# Digital_IN.net
KiCad netlist of a schematic drawn in Altium Designer
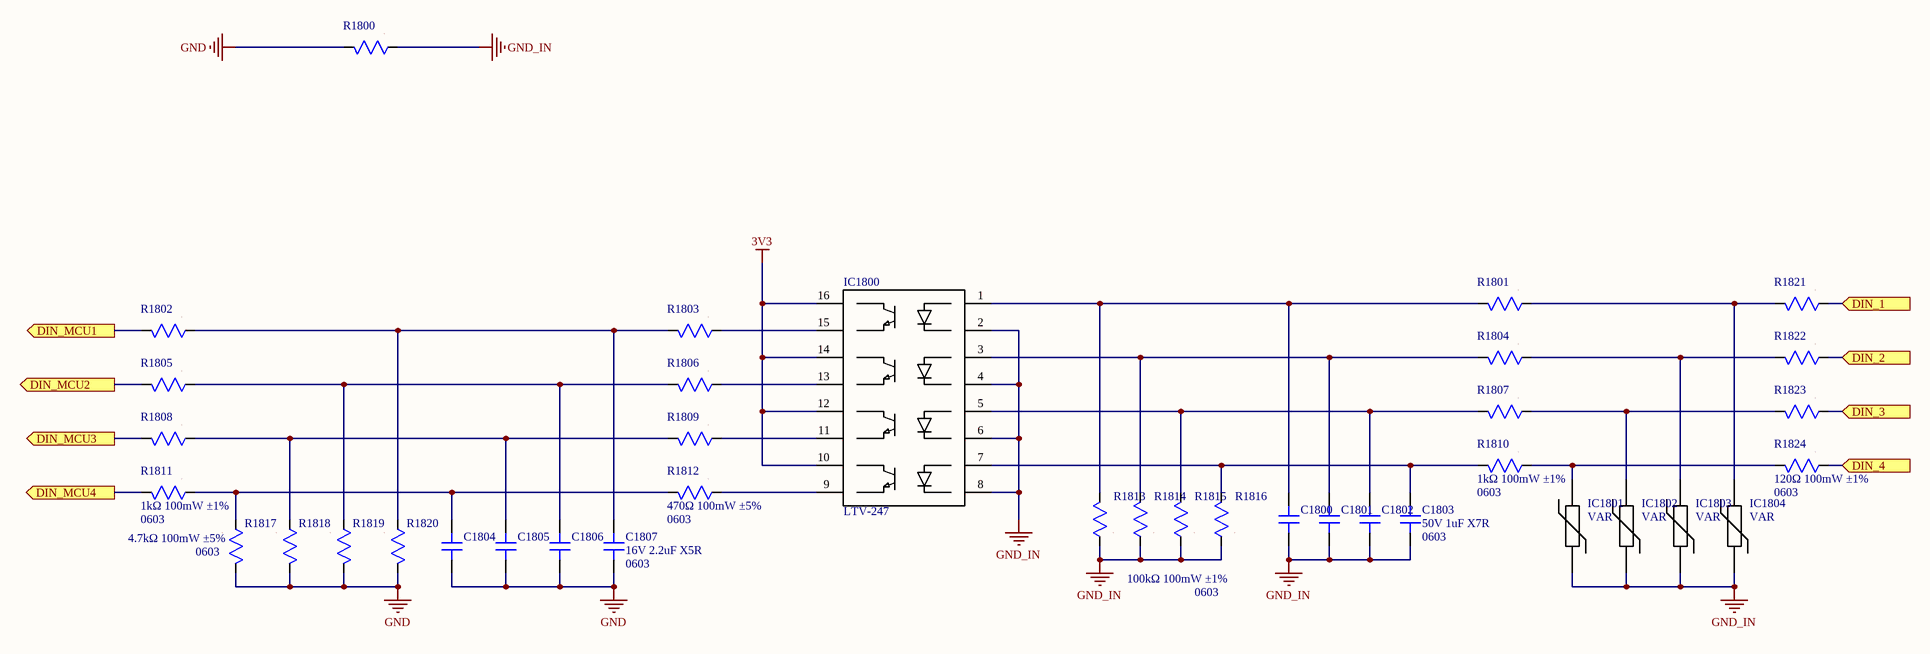
[diagram p0: Digital_IN.SchDoc]

(export (version "E")
  (design (tool "Eeschema 10.0.6"))
  (components
    (comp (ref "C1800")
      (value "CAP non polarized")
      (footprint "CAP SMD 0603")
      (description "Condensadores de cerámica multicapa (MLCC- SMD/SMT) WCAP-CSGP 1uF 50 Vol 10%")
      (fields (field (name "MPN") "885012206126") (field (name "MANUFACTURER") "Wurth Elektronik"))
      (libsource (lib "eUSR_Database") (part "CAP non polarized"))
    )
    (comp (ref "C1801")
      (value "CAP non polarized")
      (footprint "CAP SMD 0603")
      (description "Condensadores de cerámica multicapa (MLCC- SMD/SMT) WCAP-CSGP 1uF 50 Vol 10%")
      (fields (field (name "MPN") "885012206126") (field (name "MANUFACTURER") "Wurth Elektronik"))
      (libsource (lib "eUSR_Database") (part "CAP non polarized"))
    )
    (comp (ref "C1802")
      (value "CAP non polarized")
      (footprint "CAP SMD 0603")
      (description "Condensadores de cerámica multicapa (MLCC- SMD/SMT) WCAP-CSGP 1uF 50 Vol 10%")
      (fields (field (name "MPN") "885012206126") (field (name "MANUFACTURER") "Wurth Elektronik"))
      (libsource (lib "eUSR_Database") (part "CAP non polarized"))
    )
    (comp (ref "C1803")
      (value "50V 1uF X7R")
      (footprint "CAP SMD 0603")
      (description "Condensadores de cerámica multicapa (MLCC- SMD/SMT) WCAP-CSGP 1uF 50 Vol 10%")
      (fields
        (field (name "PACKAGE") "0603")
        (field (name "MPN") "885012206126")
        (field (name "MANUFACTURER") "Wurth Elektronik")
      )
      (libsource (lib "eUSR_Database") (part "CAP non polarized"))
    )
    (comp (ref "C1804")
      (value "CAP non polarized")
      (footprint "CAP SMD 0603")
      (description "Condensadores de cerámica multicapa (MLCC- SMD/SMT) WCAP-CSGP 2.2uF 16V 10%")
      (fields (field (name "MPN") "885012106029") (field (name "MANUFACTURER") "Wurth Elektronik"))
      (libsource (lib "eUSR_Database") (part "CAP non polarized"))
    )
    (comp (ref "C1805")
      (value "CAP non polarized")
      (footprint "CAP SMD 0603")
      (description "Condensadores de cerámica multicapa (MLCC- SMD/SMT) WCAP-CSGP 2.2uF 16V 10%")
      (fields (field (name "MPN") "885012106029") (field (name "MANUFACTURER") "Wurth Elektronik"))
      (libsource (lib "eUSR_Database") (part "CAP non polarized"))
    )
    (comp (ref "C1806")
      (value "CAP non polarized")
      (footprint "CAP SMD 0603")
      (description "Condensadores de cerámica multicapa (MLCC- SMD/SMT) WCAP-CSGP 2.2uF 16V 10%")
      (fields (field (name "MPN") "885012106029") (field (name "MANUFACTURER") "Wurth Elektronik"))
      (libsource (lib "eUSR_Database") (part "CAP non polarized"))
    )
    (comp (ref "C1807")
      (value "16V 2.2uF X5R")
      (footprint "CAP SMD 0603")
      (description "Condensadores de cerámica multicapa (MLCC- SMD/SMT) WCAP-CSGP 2.2uF 16V 10%")
      (fields
        (field (name "PACKAGE") "0603")
        (field (name "MPN") "885012106029")
        (field (name "MANUFACTURER") "Wurth Elektronik")
      )
      (libsource (lib "eUSR_Database") (part "CAP non polarized"))
    )
    (comp (ref "IC1800")
      (value "LTV-247")
      (footprint "SOP-16")
      (description "Optoacopladores para salidas de transistores PTR 50% 5KV 16 PIN 4CH Optocoupler")
      (fields (field (name "MANUFACTURER") "LITEON"))
      (libsource (lib "eUSR_Database") (part "LTV-247"))
    )
    (comp (ref "IC1801")
      (value "VAR")
      (footprint "VAR SMD 0805")
      (description "Varistores 18 VDC .3J 44V-CL 120A PK")
      (fields (field (name "MPN") "V18MLA0805NH") (field (name "MANUFACTURER") "Littlefuse"))
      (libsource (lib "eUSR_Database") (part "VAR"))
    )
    (comp (ref "IC1802")
      (value "VAR")
      (footprint "VAR SMD 0805")
      (description "Varistores 18 VDC .3J 44V-CL 120A PK")
      (fields (field (name "MPN") "V18MLA0805NH") (field (name "MANUFACTURER") "Littlefuse"))
      (libsource (lib "eUSR_Database") (part "VAR"))
    )
    (comp (ref "IC1803")
      (value "VAR")
      (footprint "VAR SMD 0805")
      (description "Varistores 18 VDC .3J 44V-CL 120A PK")
      (fields (field (name "MPN") "V18MLA0805NH") (field (name "MANUFACTURER") "Littlefuse"))
      (libsource (lib "eUSR_Database") (part "VAR"))
    )
    (comp (ref "IC1804")
      (value "VAR")
      (footprint "VAR SMD 0805")
      (description "Varistores 18 VDC .3J 44V-CL 120A PK")
      (fields (field (name "MPN") "V18MLA0805NH") (field (name "MANUFACTURER") "Littlefuse"))
      (libsource (lib "eUSR_Database") (part "VAR"))
    )
    (comp (ref "R1800")
      (value "RES")
      (footprint "RES SMD 0603")
      (description "Resistores de película gruesa - SMD WRIS-RSKS <0.05 Ohms 0.1 W Jumper 0603 AEC-Q200")
      (fields (field (name "MPN") "560112116001") (field (name "MANUFACTURER") "Wurth Elektronik"))
      (libsource (lib "eUSR_Database") (part "RES"))
    )
    (comp (ref "R1801")
      (value "RES")
      (footprint "RES SMD 0603")
      (description "Thick Film Resistors WRIS-RSKS 1 kOhms 1 % 0.1 W 0603 AEC-Q200")
      (fields (field (name "MPN") "560112116014") (field (name "MANUFACTURER") "Wurth Elektronik"))
      (libsource (lib "eUSR_Database") (part "RES"))
    )
    (comp (ref "R1802")
      (value "RES")
      (footprint "RES SMD 0603")
      (description "Thick Film Resistors WRIS-RSKS 1 kOhms 1 % 0.1 W 0603 AEC-Q200")
      (fields (field (name "MPN") "560112116014") (field (name "MANUFACTURER") "Wurth Elektronik"))
      (libsource (lib "eUSR_Database") (part "RES"))
    )
    (comp (ref "R1803")
      (value "RES")
      (footprint "RES SMD 0603")
      (description "Thick Film Resistors WRIS-RSKS 470 Ohms 5 % 0.1 W 0603 AEC-Q200")
      (fields (field (name "MPN") "560112116031") (field (name "MANUFACTURER") "Wurth Elektronik"))
      (libsource (lib "eUSR_Database") (part "RES"))
    )
    (comp (ref "R1804")
      (value "RES")
      (footprint "RES SMD 0603")
      (description "Thick Film Resistors WRIS-RSKS 1 kOhms 1 % 0.1 W 0603 AEC-Q200")
      (fields (field (name "MPN") "560112116014") (field (name "MANUFACTURER") "Wurth Elektronik"))
      (libsource (lib "eUSR_Database") (part "RES"))
    )
    (comp (ref "R1805")
      (value "RES")
      (footprint "RES SMD 0603")
      (description "Thick Film Resistors WRIS-RSKS 1 kOhms 1 % 0.1 W 0603 AEC-Q200")
      (fields (field (name "MPN") "560112116014") (field (name "MANUFACTURER") "Wurth Elektronik"))
      (libsource (lib "eUSR_Database") (part "RES"))
    )
    (comp (ref "R1806")
      (value "RES")
      (footprint "RES SMD 0603")
      (description "Thick Film Resistors WRIS-RSKS 470 Ohms 5 % 0.1 W 0603 AEC-Q200")
      (fields (field (name "MPN") "560112116031") (field (name "MANUFACTURER") "Wurth Elektronik"))
      (libsource (lib "eUSR_Database") (part "RES"))
    )
    (comp (ref "R1807")
      (value "RES")
      (footprint "RES SMD 0603")
      (description "Thick Film Resistors WRIS-RSKS 1 kOhms 1 % 0.1 W 0603 AEC-Q200")
      (fields (field (name "MPN") "560112116014") (field (name "MANUFACTURER") "Wurth Elektronik"))
      (libsource (lib "eUSR_Database") (part "RES"))
    )
    (comp (ref "R1808")
      (value "RES")
      (footprint "RES SMD 0603")
      (description "Thick Film Resistors WRIS-RSKS 1 kOhms 1 % 0.1 W 0603 AEC-Q200")
      (fields (field (name "MPN") "560112116014") (field (name "MANUFACTURER") "Wurth Elektronik"))
      (libsource (lib "eUSR_Database") (part "RES"))
    )
    (comp (ref "R1809")
      (value "RES")
      (footprint "RES SMD 0603")
      (description "Thick Film Resistors WRIS-RSKS 470 Ohms 5 % 0.1 W 0603 AEC-Q200")
      (fields (field (name "MPN") "560112116031") (field (name "MANUFACTURER") "Wurth Elektronik"))
      (libsource (lib "eUSR_Database") (part "RES"))
    )
    (comp (ref "R1810")
      (value "1kΩ 100mW ±1%")
      (footprint "RES SMD 0603")
      (description "Thick Film Resistors WRIS-RSKS 1 kOhms 1 % 0.1 W 0603 AEC-Q200")
      (fields
        (field (name "PACKAGE") "0603")
        (field (name "MPN") "560112116014")
        (field (name "MANUFACTURER") "Wurth Elektronik")
      )
      (libsource (lib "eUSR_Database") (part "RES"))
    )
    (comp (ref "R1811")
      (value "1kΩ 100mW ±1%")
      (footprint "RES SMD 0603")
      (description "Thick Film Resistors WRIS-RSKS 1 kOhms 1 % 0.1 W 0603 AEC-Q200")
      (fields
        (field (name "PACKAGE") "0603")
        (field (name "MPN") "560112116014")
        (field (name "MANUFACTURER") "Wurth Elektronik")
      )
      (libsource (lib "eUSR_Database") (part "RES"))
    )
    (comp (ref "R1812")
      (value "470Ω 100mW ±5%")
      (footprint "RES SMD 0603")
      (description "Thick Film Resistors WRIS-RSKS 470 Ohms 5 % 0.1 W 0603 AEC-Q200")
      (fields
        (field (name "PACKAGE") "0603")
        (field (name "MPN") "560112116031")
        (field (name "MANUFACTURER") "Wurth Elektronik")
      )
      (libsource (lib "eUSR_Database") (part "RES"))
    )
    (comp (ref "R1813")
      (value "100kΩ 100mW ±1%")
      (footprint "RES SMD 0603")
      (description "Thick Film Resistors WRIS-RSKS 100 kOhms 1 % 0.1 W 0603 AEC-Q200")
      (fields
        (field (name "PACKAGE") "0603")
        (field (name "MPN") "560112116004")
        (field (name "MANUFACTURER") "Wurth Elektronik")
      )
      (libsource (lib "eUSR_Database") (part "RES"))
    )
    (comp (ref "R1814")
      (value "RES")
      (footprint "RES SMD 0603")
      (description "Thick Film Resistors WRIS-RSKS 100 kOhms 1 % 0.1 W 0603 AEC-Q200")
      (fields (field (name "MPN") "560112116004") (field (name "MANUFACTURER") "Wurth Elektronik"))
      (libsource (lib "eUSR_Database") (part "RES"))
    )
    (comp (ref "R1815")
      (value "RES")
      (footprint "RES SMD 0603")
      (description "Thick Film Resistors WRIS-RSKS 100 kOhms 1 % 0.1 W 0603 AEC-Q200")
      (fields (field (name "MPN") "560112116004") (field (name "MANUFACTURER") "Wurth Elektronik"))
      (libsource (lib "eUSR_Database") (part "RES"))
    )
    (comp (ref "R1816")
      (value "RES")
      (footprint "RES SMD 0603")
      (description "Thick Film Resistors WRIS-RSKS 100 kOhms 1 % 0.1 W 0603 AEC-Q200")
      (fields (field (name "MPN") "560112116004") (field (name "MANUFACTURER") "Wurth Elektronik"))
      (libsource (lib "eUSR_Database") (part "RES"))
    )
    (comp (ref "R1817")
      (value "4.7kΩ 100mW ±5%")
      (footprint "RES SMD 0603")
      (description "Thick Film Resistors WRIS-RSKS 4.7 kOhms 5 % 0.1 W 0402 AEC-Q200")
      (fields
        (field (name "PACKAGE") "0603")
        (field (name "MPN") "560112110018")
        (field (name "MANUFACTURER") "Wurth Elektronik")
      )
      (libsource (lib "eUSR_Database") (part "RES"))
    )
    (comp (ref "R1818")
      (value "RES")
      (footprint "RES SMD 0603")
      (description "Thick Film Resistors WRIS-RSKS 4.7 kOhms 5 % 0.1 W 0402 AEC-Q200")
      (fields (field (name "MPN") "560112110018") (field (name "MANUFACTURER") "Wurth Elektronik"))
      (libsource (lib "eUSR_Database") (part "RES"))
    )
    (comp (ref "R1819")
      (value "RES")
      (footprint "RES SMD 0603")
      (description "Thick Film Resistors WRIS-RSKS 4.7 kOhms 5 % 0.1 W 0402 AEC-Q200")
      (fields (field (name "MPN") "560112110018") (field (name "MANUFACTURER") "Wurth Elektronik"))
      (libsource (lib "eUSR_Database") (part "RES"))
    )
    (comp (ref "R1820")
      (value "RES")
      (footprint "RES SMD 0603")
      (description "Thick Film Resistors WRIS-RSKS 4.7 kOhms 5 % 0.1 W 0402 AEC-Q200")
      (fields (field (name "MPN") "560112110018") (field (name "MANUFACTURER") "Wurth Elektronik"))
      (libsource (lib "eUSR_Database") (part "RES"))
    )
    (comp (ref "R1821")
      (value "RES")
      (footprint "RES SMD 0603")
      (description "Resistores de película gruesa - SMD WRIS-RSKS 120 Ohms 1 % 0.1 W 0603 AEC-Q200")
      (fields (field (name "MPN") "560112116119") (field (name "MANUFACTURER") "Wurth Elektronik"))
      (libsource (lib "eUSR_Database") (part "RES"))
    )
    (comp (ref "R1822")
      (value "RES")
      (footprint "RES SMD 0603")
      (description "Resistores de película gruesa - SMD WRIS-RSKS 120 Ohms 1 % 0.1 W 0603 AEC-Q200")
      (fields (field (name "MPN") "560112116119") (field (name "MANUFACTURER") "Wurth Elektronik"))
      (libsource (lib "eUSR_Database") (part "RES"))
    )
    (comp (ref "R1823")
      (value "RES")
      (footprint "RES SMD 0603")
      (description "Resistores de película gruesa - SMD WRIS-RSKS 120 Ohms 1 % 0.1 W 0603 AEC-Q200")
      (fields (field (name "MPN") "560112116119") (field (name "MANUFACTURER") "Wurth Elektronik"))
      (libsource (lib "eUSR_Database") (part "RES"))
    )
    (comp (ref "R1824")
      (value "120Ω 100mW ±1%")
      (footprint "RES SMD 0603")
      (description "Resistores de película gruesa - SMD WRIS-RSKS 120 Ohms 1 % 0.1 W 0603 AEC-Q200")
      (fields
        (field (name "PACKAGE") "0603")
        (field (name "MPN") "560112116119")
        (field (name "MANUFACTURER") "Wurth Elektronik")
      )
      (libsource (lib "eUSR_Database") (part "RES"))
    )
  )
  (nets
    (net (code "1") (name "/DIN_1") (class "Default")
      (node (ref "R1821") (pin "1") (pinfunction "1_1") (pintype "passive"))
    )
    (net (code "2") (name "/DIN_2") (class "Default")
      (node (ref "R1822") (pin "1") (pinfunction "1_1") (pintype "passive"))
    )
    (net (code "3") (name "/DIN_3") (class "Default")
      (node (ref "R1823") (pin "1") (pinfunction "1_1") (pintype "passive"))
    )
    (net (code "4") (name "/DIN_4") (class "Default")
      (node (ref "R1824") (pin "1") (pinfunction "1_1") (pintype "passive"))
    )
    (net (code "5") (name "/DIN_MCU1") (class "Default")
      (node (ref "R1802") (pin "2") (pinfunction "2_2") (pintype "passive"))
    )
    (net (code "6") (name "/DIN_MCU2") (class "Default")
      (node (ref "R1805") (pin "2") (pinfunction "2_2") (pintype "passive"))
    )
    (net (code "7") (name "/DIN_MCU3") (class "Default")
      (node (ref "R1808") (pin "2") (pinfunction "2_2") (pintype "passive"))
    )
    (net (code "8") (name "/DIN_MCU4") (class "Default")
      (node (ref "R1811") (pin "2") (pinfunction "2_2") (pintype "passive"))
    )
    (net (code "9") (name "3V3") (class "Default")
      (node (ref "IC1800") (pin "10") (pinfunction "C_4_10") (pintype "passive"))
      (node (ref "IC1800") (pin "12") (pinfunction "C_3_12") (pintype "passive"))
      (node (ref "IC1800") (pin "14") (pinfunction "C_2_14") (pintype "passive"))
      (node (ref "IC1800") (pin "16") (pinfunction "C_1_16") (pintype "passive"))
    )
    (net (code "10") (name "GND") (class "Default")
      (node (ref "C1804") (pin "2") (pinfunction "2_2") (pintype "passive"))
      (node (ref "C1805") (pin "2") (pinfunction "2_2") (pintype "passive"))
      (node (ref "C1806") (pin "2") (pinfunction "2_2") (pintype "passive"))
      (node (ref "C1807") (pin "2") (pinfunction "2_2") (pintype "passive"))
      (node (ref "R1800") (pin "2") (pinfunction "2_2") (pintype "passive"))
      (node (ref "R1817") (pin "2") (pinfunction "2_2") (pintype "passive"))
      (node (ref "R1818") (pin "2") (pinfunction "2_2") (pintype "passive"))
      (node (ref "R1819") (pin "2") (pinfunction "2_2") (pintype "passive"))
      (node (ref "R1820") (pin "2") (pinfunction "2_2") (pintype "passive"))
    )
    (net (code "11") (name "GND_IN") (class "Default")
      (node (ref "C1800") (pin "2") (pinfunction "2_2") (pintype "passive"))
      (node (ref "C1801") (pin "2") (pinfunction "2_2") (pintype "passive"))
      (node (ref "C1802") (pin "2") (pinfunction "2_2") (pintype "passive"))
      (node (ref "C1803") (pin "2") (pinfunction "2_2") (pintype "passive"))
      (node (ref "IC1800") (pin "2") (pinfunction "K_1_2") (pintype "passive"))
      (node (ref "IC1800") (pin "4") (pinfunction "K_2_4") (pintype "passive"))
      (node (ref "IC1800") (pin "6") (pinfunction "K_3_6") (pintype "passive"))
      (node (ref "IC1800") (pin "8") (pinfunction "K_4_8") (pintype "passive"))
      (node (ref "IC1801") (pin "1") (pinfunction "1_1") (pintype "passive"))
      (node (ref "IC1802") (pin "1") (pinfunction "1_1") (pintype "passive"))
      (node (ref "IC1803") (pin "1") (pinfunction "1_1") (pintype "passive"))
      (node (ref "IC1804") (pin "1") (pinfunction "1_1") (pintype "passive"))
      (node (ref "R1800") (pin "1") (pinfunction "1_1") (pintype "passive"))
      (node (ref "R1813") (pin "1") (pinfunction "1_1") (pintype "passive"))
      (node (ref "R1814") (pin "1") (pinfunction "1_1") (pintype "passive"))
      (node (ref "R1815") (pin "1") (pinfunction "1_1") (pintype "passive"))
      (node (ref "R1816") (pin "1") (pinfunction "1_1") (pintype "passive"))
    )
    (net (code "12") (name "Net-(C1804-Pad1)") (class "Default")
      (node (ref "C1804") (pin "1") (pinfunction "1_1") (pintype "passive"))
      (node (ref "R1811") (pin "1") (pinfunction "1_1") (pintype "passive"))
      (node (ref "R1812") (pin "2") (pinfunction "2_2") (pintype "passive"))
      (node (ref "R1817") (pin "1") (pinfunction "1_1") (pintype "passive"))
    )
    (net (code "13") (name "Net-(C1805-Pad1)") (class "Default")
      (node (ref "C1805") (pin "1") (pinfunction "1_1") (pintype "passive"))
      (node (ref "R1808") (pin "1") (pinfunction "1_1") (pintype "passive"))
      (node (ref "R1809") (pin "2") (pinfunction "2_2") (pintype "passive"))
      (node (ref "R1818") (pin "1") (pinfunction "1_1") (pintype "passive"))
    )
    (net (code "14") (name "Net-(C1806-Pad1)") (class "Default")
      (node (ref "C1806") (pin "1") (pinfunction "1_1") (pintype "passive"))
      (node (ref "R1805") (pin "1") (pinfunction "1_1") (pintype "passive"))
      (node (ref "R1806") (pin "2") (pinfunction "2_2") (pintype "passive"))
      (node (ref "R1819") (pin "1") (pinfunction "1_1") (pintype "passive"))
    )
    (net (code "15") (name "Net-(C1807-Pad1)") (class "Default")
      (node (ref "C1807") (pin "1") (pinfunction "1_1") (pintype "passive"))
      (node (ref "R1802") (pin "1") (pinfunction "1_1") (pintype "passive"))
      (node (ref "R1803") (pin "2") (pinfunction "2_2") (pintype "passive"))
      (node (ref "R1820") (pin "1") (pinfunction "1_1") (pintype "passive"))
    )
    (net (code "16") (name "Net-(IC1800-A_1)") (class "Default")
      (node (ref "C1800") (pin "1") (pinfunction "1_1") (pintype "passive"))
      (node (ref "IC1800") (pin "1") (pinfunction "A_1_1") (pintype "passive"))
      (node (ref "R1801") (pin "2") (pinfunction "2_2") (pintype "passive"))
      (node (ref "R1813") (pin "2") (pinfunction "2_2") (pintype "passive"))
    )
    (net (code "17") (name "Net-(IC1800-A_2)") (class "Default")
      (node (ref "C1801") (pin "1") (pinfunction "1_1") (pintype "passive"))
      (node (ref "IC1800") (pin "3") (pinfunction "A_2_3") (pintype "passive"))
      (node (ref "R1804") (pin "2") (pinfunction "2_2") (pintype "passive"))
      (node (ref "R1814") (pin "2") (pinfunction "2_2") (pintype "passive"))
    )
    (net (code "18") (name "Net-(IC1800-A_3)") (class "Default")
      (node (ref "C1802") (pin "1") (pinfunction "1_1") (pintype "passive"))
      (node (ref "IC1800") (pin "5") (pinfunction "A_3_5") (pintype "passive"))
      (node (ref "R1807") (pin "2") (pinfunction "2_2") (pintype "passive"))
      (node (ref "R1815") (pin "2") (pinfunction "2_2") (pintype "passive"))
    )
    (net (code "19") (name "Net-(IC1800-A_4)") (class "Default")
      (node (ref "C1803") (pin "1") (pinfunction "1_1") (pintype "passive"))
      (node (ref "IC1800") (pin "7") (pinfunction "A_4_7") (pintype "passive"))
      (node (ref "R1810") (pin "2") (pinfunction "2_2") (pintype "passive"))
      (node (ref "R1816") (pin "2") (pinfunction "2_2") (pintype "passive"))
    )
    (net (code "20") (name "Net-(IC1800-E_1)") (class "Default")
      (node (ref "IC1800") (pin "15") (pinfunction "E_1_15") (pintype "passive"))
      (node (ref "R1803") (pin "1") (pinfunction "1_1") (pintype "passive"))
    )
    (net (code "21") (name "Net-(IC1800-E_2)") (class "Default")
      (node (ref "IC1800") (pin "13") (pinfunction "E_2_13") (pintype "passive"))
      (node (ref "R1806") (pin "1") (pinfunction "1_1") (pintype "passive"))
    )
    (net (code "22") (name "Net-(IC1800-E_3)") (class "Default")
      (node (ref "IC1800") (pin "11") (pinfunction "E_3_11") (pintype "passive"))
      (node (ref "R1809") (pin "1") (pinfunction "1_1") (pintype "passive"))
    )
    (net (code "23") (name "Net-(IC1800-E_4)") (class "Default")
      (node (ref "IC1800") (pin "9") (pinfunction "E_4_9") (pintype "passive"))
      (node (ref "R1812") (pin "1") (pinfunction "1_1") (pintype "passive"))
    )
    (net (code "24") (name "Net-(IC1801-Pad2)") (class "Default")
      (node (ref "IC1801") (pin "2") (pinfunction "2_2") (pintype "passive"))
      (node (ref "R1810") (pin "1") (pinfunction "1_1") (pintype "passive"))
      (node (ref "R1824") (pin "2") (pinfunction "2_2") (pintype "passive"))
    )
    (net (code "25") (name "Net-(IC1802-Pad2)") (class "Default")
      (node (ref "IC1802") (pin "2") (pinfunction "2_2") (pintype "passive"))
      (node (ref "R1807") (pin "1") (pinfunction "1_1") (pintype "passive"))
      (node (ref "R1823") (pin "2") (pinfunction "2_2") (pintype "passive"))
    )
    (net (code "26") (name "Net-(IC1803-Pad2)") (class "Default")
      (node (ref "IC1803") (pin "2") (pinfunction "2_2") (pintype "passive"))
      (node (ref "R1804") (pin "1") (pinfunction "1_1") (pintype "passive"))
      (node (ref "R1822") (pin "2") (pinfunction "2_2") (pintype "passive"))
    )
    (net (code "27") (name "Net-(IC1804-Pad2)") (class "Default")
      (node (ref "IC1804") (pin "2") (pinfunction "2_2") (pintype "passive"))
      (node (ref "R1801") (pin "1") (pinfunction "1_1") (pintype "passive"))
      (node (ref "R1821") (pin "2") (pinfunction "2_2") (pintype "passive"))
    )
  )
)
